# ALLEGRO_CONNECTOR.net
KiCad netlist of a schematic drawn in Altium Designer
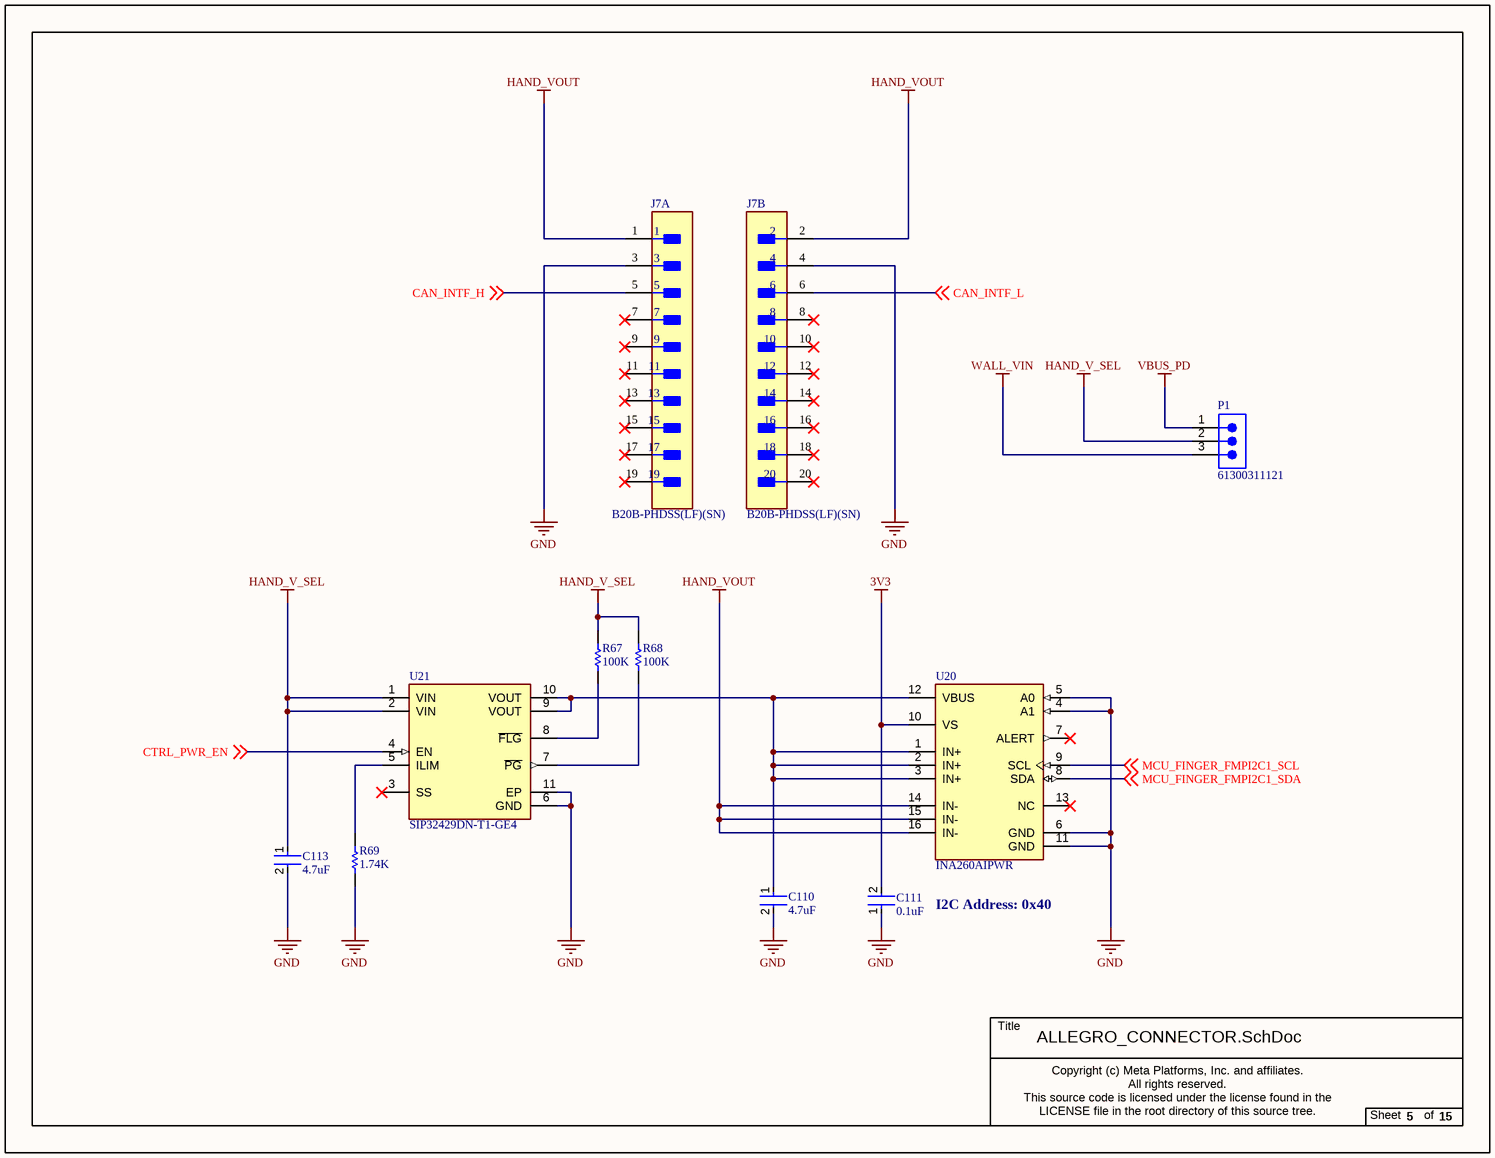
[diagram p0: ALLEGRO_CONNECTOR.SchDoc]

(export (version "E")
  (design (tool "Eeschema 10.0.6"))
  (components
    (comp (ref "C110")
      (value "4.7uF")
      (footprint "FP-1210-L_3_2_0_3-W_2_5_0-IPC_B")
      (description "None")
      (libsource (lib "Altium Content Vault") (part "02cd4be3c70576c341d710602a673aa"))
    )
    (comp (ref "C111")
      (value "0.1uF")
      (footprint "FP-CC0201-BA-MFG")
      (description "CAP CER 0.1UF 6.3V X5R 0201")
      (fields (field (name "MANUFACTURER") "Yageo") (field (name "TOLERANCE") "0.1"))
      (libsource (lib "Altium Content Vault") (part "11868f565c42a9108669ba33697ecf6"))
    )
    (comp (ref "C113")
      (value "4.7uF")
      (footprint "FP-1210-L_3_2_0_3-W_2_5_0-IPC_B")
      (description "None")
      (libsource (lib "Altium Content Vault") (part "02cd4be3c70576c341d710602a673aa"))
    )
    (comp (ref "J7")
      (value "B20B-PHDSS(LF)(SN)")
      (footprint "FP-B20B-PHDSS_LF_SN-MFG")
      (description "CONN HEADER VERT 20POS 2MM")
      (libsource (lib "") (part "1a707746965fe418eefa586b9e0ef91_1"))
    )
    (comp (ref "P1")
      (value "61300311121")
      (footprint "61300311121")
      (libsource (lib "Altium Content Vault") (part "Header_Male_1R_03P"))
    )
    (comp (ref "R67")
      (value "100K")
      (footprint "RESC1005X40X25NL05T10")
      (fields (field (name "PART NUMBER") "RC0402FR-07100KL") (field (name "MANUFACTURER") "Yageo / Phycomp"))
      (libsource (lib "Altium Content Vault") (part "RES"))
    )
    (comp (ref "R68")
      (value "100K")
      (footprint "RESC1005X40X25NL05T10")
      (fields (field (name "PART NUMBER") "RC0402FR-07100KL") (field (name "MANUFACTURER") "Yageo / Phycomp"))
      (libsource (lib "Altium Content Vault") (part "RES"))
    )
    (comp (ref "R69")
      (value "1.74K")
      (footprint "RESC1005X35X20ML05T10")
      (fields
        (field (name "MANUFACTURER") "TE Connectivity / AMP")
        (field (name "PART NUMBER") "CPF0402B1K74E1")
      )
      (libsource (lib "Altium Content Vault") (part "RES"))
    )
    (comp (ref "U20")
      (value "INA260AIPWR")
      (footprint "FP-PW0016A-MFG")
      (description "IC MONITOR PWR/CURR 16TSSOP")
      (fields
        (field (name "MANUFACTURER") "Texas Instruments")
        (field (name "OCTOPART") "https://octopart.com/ina260aipwr-texas+instruments-75199489")
      )
      (libsource (lib "Altium Content Vault") (part "fcceeca0fd405d0f0207f40a7ff7922"))
    )
    (comp (ref "U21")
      (value "SIP32429DN-T1-GE4")
      (footprint "FP-S-42134-IPC_C")
      (description "IC PWR SWITCH P-CHAN 1:1 10DFN")
      (libsource (lib "Altium Content Vault") (part "e6471fc6769e245475fdc1f931f6455"))
    )
  )
  (nets
    (net (code "1") (name "3V3") (class "Default")
      (node (ref "C111") (pin "2") (pinfunction "2_2") (pintype "passive"))
      (node (ref "U20") (pin "10") (pinfunction "VS_10") (pintype "passive"))
    )
    (net (code "2") (name "CAN_INTF_H") (class "Default")
      (node (ref "J7") (pin "5") (pinfunction "5_5") (pintype "passive"))
    )
    (net (code "3") (name "CAN_INTF_L") (class "Default")
      (node (ref "J7") (pin "6") (pinfunction "6_6") (pintype "passive"))
    )
    (net (code "4") (name "CTRL_PWR_EN") (class "Default")
      (node (ref "U21") (pin "4") (pinfunction "EN_4") (pintype "input"))
    )
    (net (code "5") (name "GND") (class "Default")
      (node (ref "C110") (pin "2") (pinfunction "2_2") (pintype "passive"))
      (node (ref "C111") (pin "1") (pinfunction "1_1") (pintype "passive"))
      (node (ref "C113") (pin "2") (pinfunction "2_2") (pintype "passive"))
      (node (ref "J7") (pin "3") (pinfunction "3_3") (pintype "passive"))
      (node (ref "J7") (pin "4") (pinfunction "4_4") (pintype "passive"))
      (node (ref "R69") (pin "1") (pinfunction "1_1") (pintype "passive"))
      (node (ref "U20") (pin "11") (pinfunction "GND_11") (pintype "power_in"))
      (node (ref "U20") (pin "4") (pinfunction "A1_4") (pintype "input"))
      (node (ref "U20") (pin "5") (pinfunction "A0_5") (pintype "input"))
      (node (ref "U20") (pin "6") (pinfunction "GND_6") (pintype "power_in"))
      (node (ref "U21") (pin "11") (pinfunction "EP_11") (pintype "passive"))
      (node (ref "U21") (pin "6") (pinfunction "GND_6") (pintype "power_in"))
    )
    (net (code "6") (name "HAND_VOUT") (class "Default")
      (node (ref "J7") (pin "1") (pinfunction "1_1") (pintype "passive"))
      (node (ref "J7") (pin "2") (pinfunction "2_2") (pintype "passive"))
      (node (ref "U20") (pin "14") (pinfunction "IN-_14") (pintype "passive"))
      (node (ref "U20") (pin "15") (pinfunction "IN-_15") (pintype "passive"))
      (node (ref "U20") (pin "16") (pinfunction "IN-_16") (pintype "passive"))
    )
    (net (code "7") (name "HAND_V_SEL") (class "Default")
      (node (ref "C113") (pin "1") (pinfunction "1_1") (pintype "passive"))
      (node (ref "P1") (pin "2") (pinfunction "2_2") (pintype "passive"))
      (node (ref "R67") (pin "2") (pinfunction "2_2") (pintype "passive"))
      (node (ref "R68") (pin "2") (pinfunction "2_2") (pintype "passive"))
      (node (ref "U21") (pin "1") (pinfunction "VIN_1") (pintype "power_in"))
      (node (ref "U21") (pin "2") (pinfunction "VIN_2") (pintype "power_in"))
    )
    (net (code "8") (name "MCU_FINGER_FMPI2C1_SCL") (class "Default")
      (node (ref "U20") (pin "9") (pinfunction "SCL_9") (pintype "input"))
    )
    (net (code "9") (name "MCU_FINGER_FMPI2C1_SDA") (class "Default")
      (node (ref "U20") (pin "8") (pinfunction "SDA_8") (pintype "bidirectional"))
    )
    (net (code "10") (name "Net-(U20-VBUS)") (class "Default")
      (node (ref "C110") (pin "1") (pinfunction "1_1") (pintype "passive"))
      (node (ref "U20") (pin "1") (pinfunction "IN+_1") (pintype "passive"))
      (node (ref "U20") (pin "12") (pinfunction "VBUS_12") (pintype "passive"))
      (node (ref "U20") (pin "2") (pinfunction "IN+_2") (pintype "passive"))
      (node (ref "U20") (pin "3") (pinfunction "IN+_3") (pintype "passive"))
      (node (ref "U21") (pin "10") (pinfunction "VOUT_10") (pintype "power_in"))
      (node (ref "U21") (pin "9") (pinfunction "VOUT_9") (pintype "power_in"))
    )
    (net (code "11") (name "Net-(U21-ILIM)") (class "Default")
      (node (ref "R69") (pin "2") (pinfunction "2_2") (pintype "passive"))
      (node (ref "U21") (pin "5") (pinfunction "ILIM_5") (pintype "passive"))
    )
    (net (code "12") (name "Net-(U21-~{FLG})") (class "Default")
      (node (ref "R67") (pin "1") (pinfunction "1_1") (pintype "passive"))
      (node (ref "U21") (pin "8") (pinfunction "~{FLG}_8") (pintype "open_collector"))
    )
    (net (code "13") (name "Net-(U21-~{PG})") (class "Default")
      (node (ref "R68") (pin "1") (pinfunction "1_1") (pintype "passive"))
      (node (ref "U21") (pin "7") (pinfunction "~{PG}_7") (pintype "output"))
    )
    (net (code "14") (name "VBUS_PD") (class "Default")
      (node (ref "P1") (pin "1") (pinfunction "1_1") (pintype "passive"))
    )
    (net (code "15") (name "WALL_VIN") (class "Default")
      (node (ref "P1") (pin "3") (pinfunction "3_3") (pintype "passive"))
    )
    (net (code "16") (name "unconnected-(J7-Pad7)") (class "Default")
      (node (ref "J7") (pin "7") (pinfunction "7_7") (pintype "passive+no_connect"))
    )
    (net (code "17") (name "unconnected-(J7-Pad8)") (class "Default")
      (node (ref "J7") (pin "8") (pinfunction "8_8") (pintype "passive+no_connect"))
    )
    (net (code "18") (name "unconnected-(J7-Pad9)") (class "Default")
      (node (ref "J7") (pin "9") (pinfunction "9_9") (pintype "passive+no_connect"))
    )
    (net (code "19") (name "unconnected-(J7-Pad10)") (class "Default")
      (node (ref "J7") (pin "10") (pinfunction "10_10") (pintype "passive+no_connect"))
    )
    (net (code "20") (name "unconnected-(J7-Pad11)") (class "Default")
      (node (ref "J7") (pin "11") (pinfunction "11_11") (pintype "passive+no_connect"))
    )
    (net (code "21") (name "unconnected-(J7-Pad12)") (class "Default")
      (node (ref "J7") (pin "12") (pinfunction "12_12") (pintype "passive+no_connect"))
    )
    (net (code "22") (name "unconnected-(J7-Pad13)") (class "Default")
      (node (ref "J7") (pin "13") (pinfunction "13_13") (pintype "passive+no_connect"))
    )
    (net (code "23") (name "unconnected-(J7-Pad14)") (class "Default")
      (node (ref "J7") (pin "14") (pinfunction "14_14") (pintype "passive+no_connect"))
    )
    (net (code "24") (name "unconnected-(J7-Pad15)") (class "Default")
      (node (ref "J7") (pin "15") (pinfunction "15_15") (pintype "passive+no_connect"))
    )
    (net (code "25") (name "unconnected-(J7-Pad16)") (class "Default")
      (node (ref "J7") (pin "16") (pinfunction "16_16") (pintype "passive+no_connect"))
    )
    (net (code "26") (name "unconnected-(J7-Pad17)") (class "Default")
      (node (ref "J7") (pin "17") (pinfunction "17_17") (pintype "passive+no_connect"))
    )
    (net (code "27") (name "unconnected-(J7-Pad18)") (class "Default")
      (node (ref "J7") (pin "18") (pinfunction "18_18") (pintype "passive+no_connect"))
    )
    (net (code "28") (name "unconnected-(J7-Pad19)") (class "Default")
      (node (ref "J7") (pin "19") (pinfunction "19_19") (pintype "passive+no_connect"))
    )
    (net (code "29") (name "unconnected-(J7-Pad20)") (class "Default")
      (node (ref "J7") (pin "20") (pinfunction "20_20") (pintype "passive+no_connect"))
    )
    (net (code "30") (name "unconnected-(U20-ALERT-Pad7)") (class "Default")
      (node (ref "U20") (pin "7") (pinfunction "ALERT_7") (pintype "output+no_connect"))
    )
    (net (code "31") (name "unconnected-(U20-NC-Pad13)") (class "Default")
      (node (ref "U20") (pin "13") (pinfunction "NC_13") (pintype "passive+no_connect"))
    )
    (net (code "32") (name "unconnected-(U21-SS-Pad3)") (class "Default")
      (node (ref "U21") (pin "3") (pinfunction "SS_3") (pintype "passive+no_connect"))
    )
  )
)
